# WheatStoneBridge.net
KiCad netlist of a schematic drawn in Altium Designer
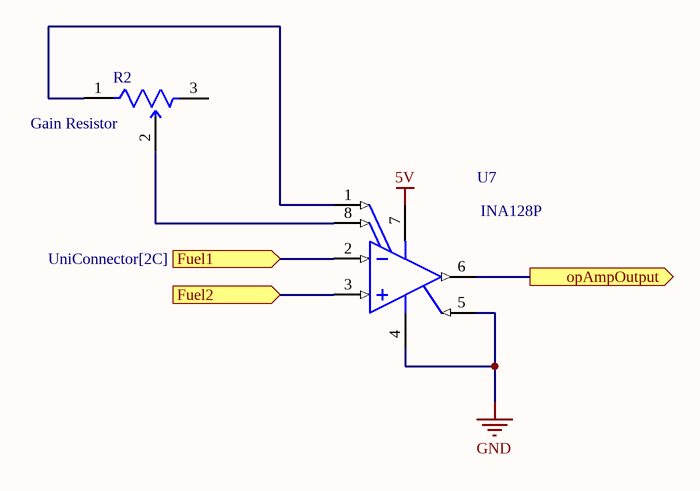
[diagram p0: WheatStoneBridge.SchDoc]

(export (version "E")
  (design (tool "Eeschema 10.0.6"))
  (components
    (comp (ref "R2")
      (value "Gain Resistor")
      (footprint "FP-3296W-MFG")
      (description "TRIMMER 200K OHM 0.5W PC PIN TOP")
      (fields (field (name "TOLERANCE") "10%"))
      (libsource (lib "Altium Content Vault") (part "2dcfd2547301a7d3209a5e99acfd772"))
    )
    (comp (ref "U7")
      (value "INA128P")
      (footprint "P0008A")
      (fields (field (name "MANUFACTURER") "Texas Instruments"))
      (libsource (lib "Altium Content Vault") (part "TI-INA1XX-8"))
    )
  )
  (nets
    (net (code "1") (name "/Fuel1") (class "Default")
      (node (ref "U7") (pin "2") (pinfunction "VIN-_2") (pintype "input"))
    )
    (net (code "2") (name "/Fuel2") (class "Default")
      (node (ref "U7") (pin "3") (pinfunction "VIN+_3") (pintype "input"))
    )
    (net (code "3") (name "/opAmpOutput") (class "Default")
      (node (ref "U7") (pin "6") (pinfunction "VO_6") (pintype "output"))
    )
    (net (code "4") (name "5V") (class "Default")
      (node (ref "U7") (pin "7") (pinfunction "V+_7") (pintype "power_in"))
    )
    (net (code "5") (name "GND") (class "Default")
      (node (ref "U7") (pin "4") (pinfunction "V-_4") (pintype "power_in"))
      (node (ref "U7") (pin "5") (pinfunction "REF_5") (pintype "input"))
    )
    (net (code "6") (name "Net-(R2-CCW)") (class "Default")
      (node (ref "R2") (pin "1") (pinfunction "CCW_1") (pintype "passive"))
      (node (ref "U7") (pin "1") (pinfunction "RG_1") (pintype "input"))
    )
    (net (code "7") (name "Net-(R2-WIPER)") (class "Default")
      (node (ref "R2") (pin "2") (pinfunction "WIPER_2") (pintype "passive"))
      (node (ref "U7") (pin "8") (pinfunction "RG_8") (pintype "input"))
    )
    (net (code "8") (name "unconnected-(R2-CW-Pad3)") (class "Default")
      (node (ref "R2") (pin "3") (pinfunction "CW_3") (pintype "passive"))
    )
  )
)
